# LEDline.net
KiCad netlist of a schematic drawn in EAGLE
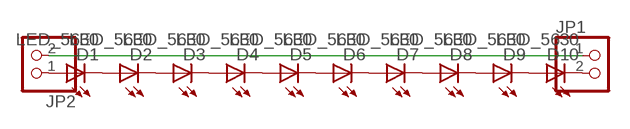
[diagram p0: schematic, sheet 1]

(export (version "E")
  (design (tool "Eeschema 10.0.6"))
  (components
    (comp (ref "D1")
      (value "LED_5630")
      (footprint "eagle-import:LED5730")
      (libsource (lib "eagle-import") (part "LED_5630"))
    )
    (comp (ref "D2")
      (value "LED_5630")
      (footprint "eagle-import:LED5730")
      (libsource (lib "eagle-import") (part "LED_5630"))
    )
    (comp (ref "D3")
      (value "LED_5630")
      (footprint "eagle-import:LED5730")
      (libsource (lib "eagle-import") (part "LED_5630"))
    )
    (comp (ref "D4")
      (value "LED_5630")
      (footprint "eagle-import:LED5730")
      (libsource (lib "eagle-import") (part "LED_5630"))
    )
    (comp (ref "D5")
      (value "LED_5630")
      (footprint "eagle-import:LED5730")
      (libsource (lib "eagle-import") (part "LED_5630"))
    )
    (comp (ref "D6")
      (value "LED_5630")
      (footprint "eagle-import:LED5730")
      (libsource (lib "eagle-import") (part "LED_5630"))
    )
    (comp (ref "D7")
      (value "LED_5630")
      (footprint "eagle-import:LED5730")
      (libsource (lib "eagle-import") (part "LED_5630"))
    )
    (comp (ref "D8")
      (value "LED_5630")
      (footprint "eagle-import:LED5730")
      (libsource (lib "eagle-import") (part "LED_5630"))
    )
    (comp (ref "D9")
      (value "LED_5630")
      (footprint "eagle-import:LED5730")
      (libsource (lib "eagle-import") (part "LED_5630"))
    )
    (comp (ref "D10")
      (value "LED_5630")
      (footprint "eagle-import:LED5730")
      (libsource (lib "eagle-import") (part "LED_5630"))
    )
    (comp (ref "JP1")
      (value "PINHD-1X2/90")
      (footprint "eagle-import:1X02_90")
      (libsource (lib "eagle-import") (part "PINHD-1X2/90"))
    )
    (comp (ref "JP2")
      (value "PINHD-1X2/90")
      (footprint "eagle-import:1X02_90")
      (libsource (lib "eagle-import") (part "PINHD-1X2/90"))
    )
  )
  (nets
    (net (code "1") (name "Net-(D1-A-PadA1)") (class "Default")
      (node (ref "D1") (pin "A") (pinfunction "A_A") (pintype "passive"))
      (node (ref "D1") (pin "A1") (pinfunction "A_A1") (pintype "passive"))
      (node (ref "JP2") (pin "1") (pinfunction "1_1") (pintype "passive"))
    )
    (net (code "2") (name "Net-(D1-PadC)") (class "Default")
      (node (ref "D1") (pin "C") (pinfunction "C_C") (pintype "passive"))
      (node (ref "D2") (pin "A") (pinfunction "A_A") (pintype "passive"))
      (node (ref "D2") (pin "A1") (pinfunction "A_A1") (pintype "passive"))
    )
    (net (code "3") (name "Net-(D2-PadC)") (class "Default")
      (node (ref "D2") (pin "C") (pinfunction "C_C") (pintype "passive"))
      (node (ref "D3") (pin "A") (pinfunction "A_A") (pintype "passive"))
      (node (ref "D3") (pin "A1") (pinfunction "A_A1") (pintype "passive"))
    )
    (net (code "4") (name "Net-(D3-PadC)") (class "Default")
      (node (ref "D3") (pin "C") (pinfunction "C_C") (pintype "passive"))
      (node (ref "D4") (pin "A") (pinfunction "A_A") (pintype "passive"))
      (node (ref "D4") (pin "A1") (pinfunction "A_A1") (pintype "passive"))
    )
    (net (code "5") (name "Net-(D4-PadC)") (class "Default")
      (node (ref "D4") (pin "C") (pinfunction "C_C") (pintype "passive"))
      (node (ref "D5") (pin "A") (pinfunction "A_A") (pintype "passive"))
      (node (ref "D5") (pin "A1") (pinfunction "A_A1") (pintype "passive"))
    )
    (net (code "6") (name "Net-(D5-PadC)") (class "Default")
      (node (ref "D5") (pin "C") (pinfunction "C_C") (pintype "passive"))
      (node (ref "D6") (pin "A") (pinfunction "A_A") (pintype "passive"))
      (node (ref "D6") (pin "A1") (pinfunction "A_A1") (pintype "passive"))
    )
    (net (code "7") (name "Net-(D6-PadC)") (class "Default")
      (node (ref "D6") (pin "C") (pinfunction "C_C") (pintype "passive"))
      (node (ref "D7") (pin "A") (pinfunction "A_A") (pintype "passive"))
      (node (ref "D7") (pin "A1") (pinfunction "A_A1") (pintype "passive"))
    )
    (net (code "8") (name "Net-(D7-PadC)") (class "Default")
      (node (ref "D7") (pin "C") (pinfunction "C_C") (pintype "passive"))
      (node (ref "D8") (pin "A") (pinfunction "A_A") (pintype "passive"))
      (node (ref "D8") (pin "A1") (pinfunction "A_A1") (pintype "passive"))
    )
    (net (code "9") (name "Net-(D8-PadC)") (class "Default")
      (node (ref "D8") (pin "C") (pinfunction "C_C") (pintype "passive"))
      (node (ref "D9") (pin "A") (pinfunction "A_A") (pintype "passive"))
      (node (ref "D9") (pin "A1") (pinfunction "A_A1") (pintype "passive"))
    )
    (net (code "10") (name "Net-(D10-A-PadA1)") (class "Default")
      (node (ref "D10") (pin "A") (pinfunction "A_A") (pintype "passive"))
      (node (ref "D10") (pin "A1") (pinfunction "A_A1") (pintype "passive"))
      (node (ref "D9") (pin "C") (pinfunction "C_C") (pintype "passive"))
    )
    (net (code "11") (name "Net-(D10-PadC)") (class "Default")
      (node (ref "D10") (pin "C") (pinfunction "C_C") (pintype "passive"))
      (node (ref "JP1") (pin "2") (pinfunction "2_2") (pintype "passive"))
    )
    (net (code "12") (name "Net-(JP1-Pad1)") (class "Default")
      (node (ref "JP1") (pin "1") (pinfunction "1_1") (pintype "passive"))
      (node (ref "JP2") (pin "2") (pinfunction "2_2") (pintype "passive"))
    )
  )
)
